# mt10_redraw.net
KiCad netlist of a schematic drawn in EAGLE
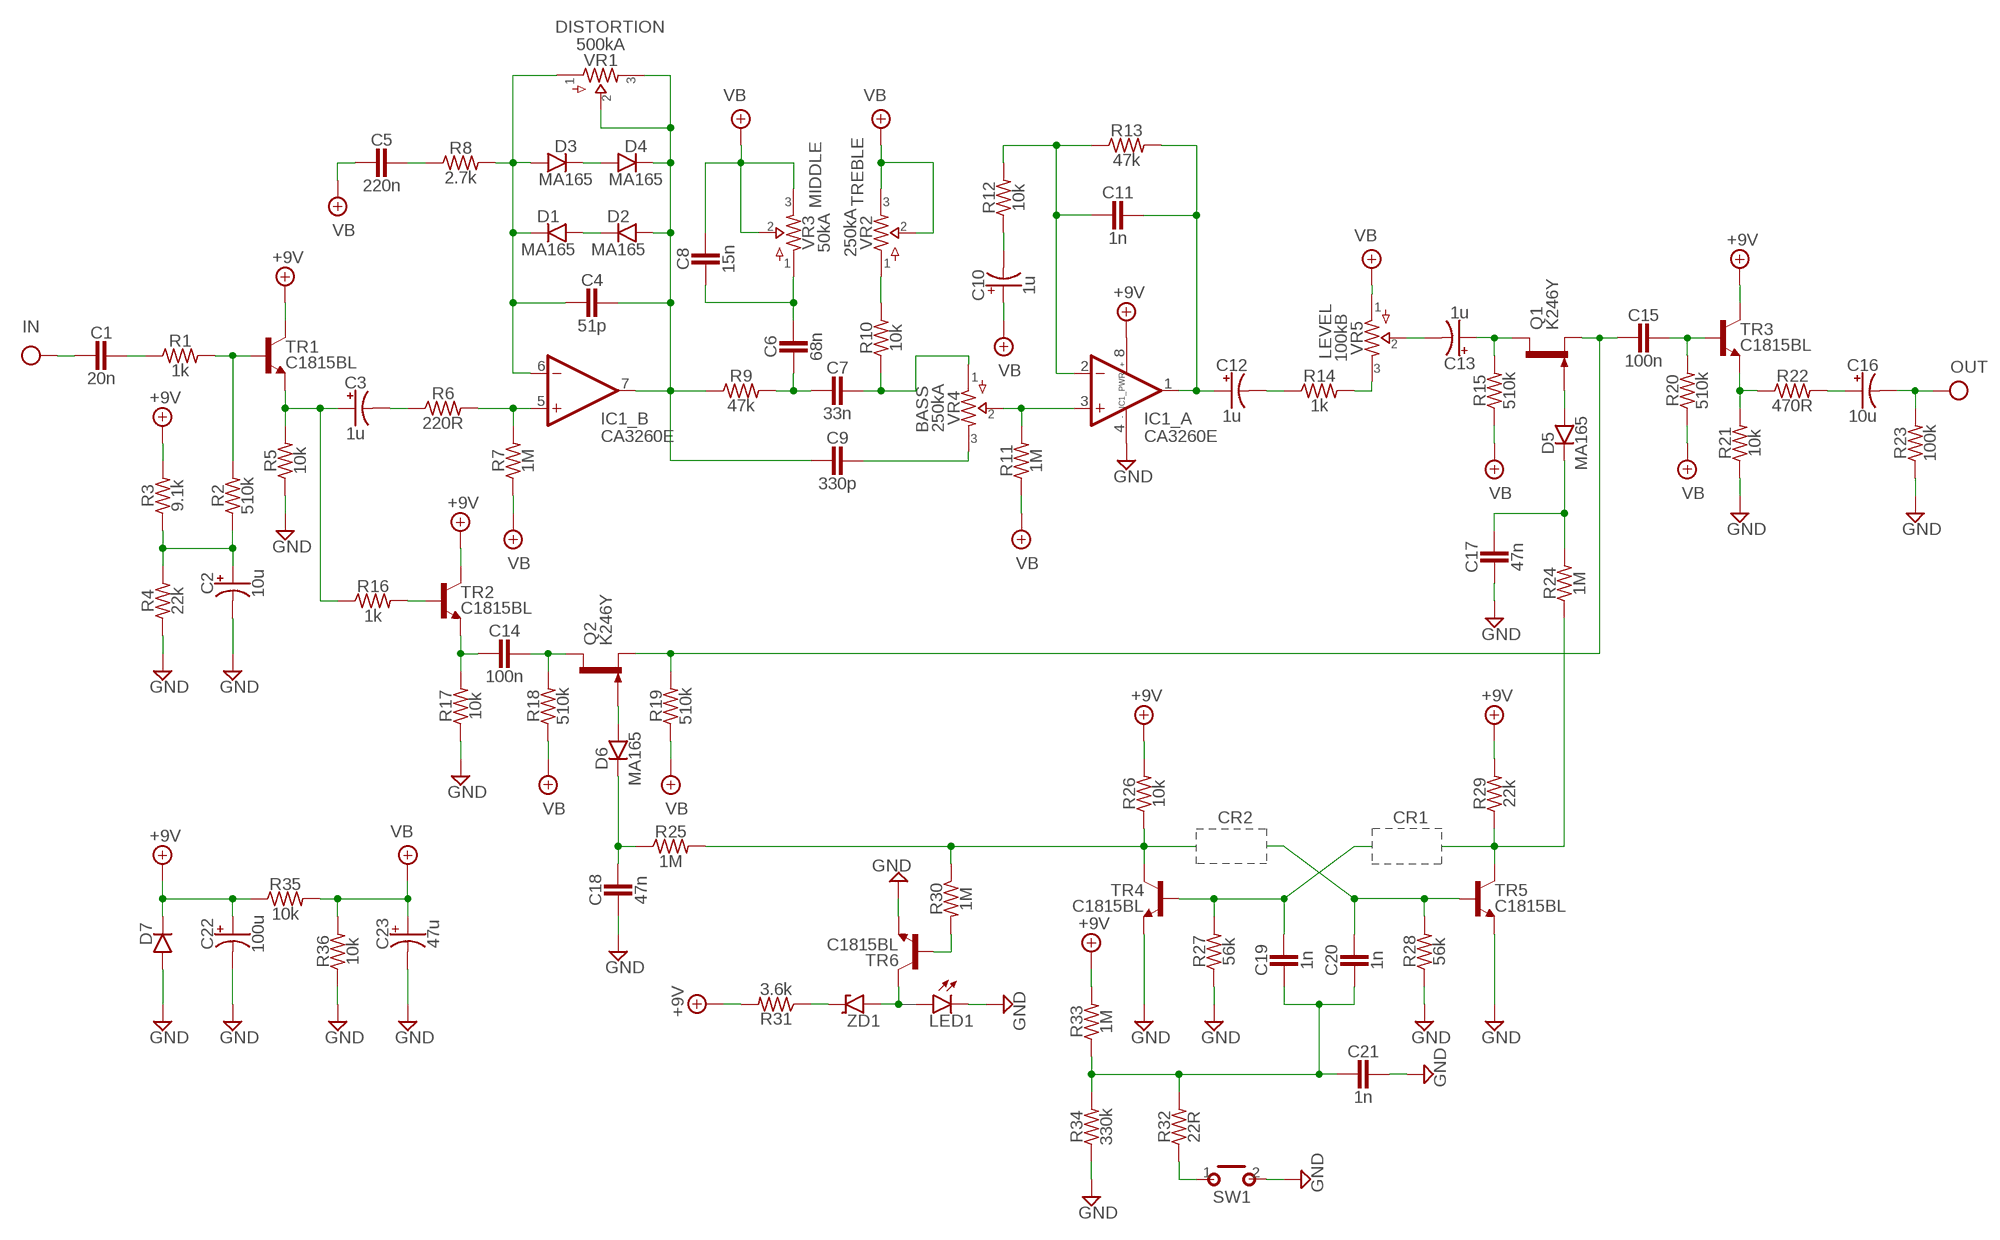
[diagram p0: schematic, sheet 1]

(export (version "E")
  (design (tool "Eeschema 10.0.6"))
  (components
    (comp (ref "C1")
      (value "20n")
      (footprint "eagle-import:BOX_SMALL")
      (libsource (lib "eagle-import") (part "CER/FILMBOX.1"))
    )
    (comp (ref "C2")
      (value "10u")
      (footprint "eagle-import:050_020")
      (libsource (lib "eagle-import") (part "0500"))
    )
    (comp (ref "C3")
      (value "1u")
      (footprint "eagle-import:050_020")
      (libsource (lib "eagle-import") (part "0500"))
    )
    (comp (ref "C4")
      (value "51p")
      (footprint "eagle-import:BOX_SMALL")
      (libsource (lib "eagle-import") (part "CER/FILMBOX.1"))
    )
    (comp (ref "C5")
      (value "220n")
      (footprint "eagle-import:BOX_SMALL")
      (libsource (lib "eagle-import") (part "CER/FILMBOX.1"))
    )
    (comp (ref "C6")
      (value "68n")
      (footprint "eagle-import:BOX_SMALL")
      (libsource (lib "eagle-import") (part "CER/FILMBOX.1"))
    )
    (comp (ref "C7")
      (value "33n")
      (footprint "eagle-import:BOX_SMALL")
      (libsource (lib "eagle-import") (part "CER/FILMBOX.1"))
    )
    (comp (ref "C8")
      (value "15n")
      (footprint "eagle-import:BOX_SMALL")
      (libsource (lib "eagle-import") (part "CER/FILMBOX.1"))
    )
    (comp (ref "C9")
      (value "330p")
      (footprint "eagle-import:BOX_SMALL")
      (libsource (lib "eagle-import") (part "CER/FILMBOX.1"))
    )
    (comp (ref "C10")
      (value "1u")
      (footprint "eagle-import:050_020")
      (libsource (lib "eagle-import") (part "0500"))
    )
    (comp (ref "C11")
      (value "1n")
      (footprint "eagle-import:BOX_SMALL")
      (libsource (lib "eagle-import") (part "CER/FILMBOX.1"))
    )
    (comp (ref "C12")
      (value "1u")
      (footprint "eagle-import:050_020")
      (libsource (lib "eagle-import") (part "0500"))
    )
    (comp (ref "C13")
      (value "1u")
      (footprint "eagle-import:050_020")
      (libsource (lib "eagle-import") (part "0500"))
    )
    (comp (ref "C14")
      (value "100n")
      (footprint "eagle-import:BOX_SMALL")
      (libsource (lib "eagle-import") (part "CER/FILMBOX.1"))
    )
    (comp (ref "C15")
      (value "100n")
      (footprint "eagle-import:BOX_SMALL")
      (libsource (lib "eagle-import") (part "CER/FILMBOX.1"))
    )
    (comp (ref "C16")
      (value "10u")
      (footprint "eagle-import:050_020")
      (libsource (lib "eagle-import") (part "0500"))
    )
    (comp (ref "C17")
      (value "47n")
      (footprint "eagle-import:BOX_SMALL")
      (libsource (lib "eagle-import") (part "CER/FILMBOX.1"))
    )
    (comp (ref "C18")
      (value "47n")
      (footprint "eagle-import:BOX_SMALL")
      (libsource (lib "eagle-import") (part "CER/FILMBOX.1"))
    )
    (comp (ref "C19")
      (value "1n")
      (footprint "eagle-import:BOX_SMALL")
      (libsource (lib "eagle-import") (part "CER/FILMBOX.1"))
    )
    (comp (ref "C20")
      (value "1n")
      (footprint "eagle-import:BOX_SMALL")
      (libsource (lib "eagle-import") (part "CER/FILMBOX.1"))
    )
    (comp (ref "C21")
      (value "1n")
      (footprint "eagle-import:BOX_SMALL")
      (libsource (lib "eagle-import") (part "CER/FILMBOX.1"))
    )
    (comp (ref "C22")
      (value "100u")
      (footprint "eagle-import:050_020")
      (libsource (lib "eagle-import") (part "0500"))
    )
    (comp (ref "C23")
      (value "47u")
      (footprint "eagle-import:050_020")
      (libsource (lib "eagle-import") (part "0500"))
    )
    (comp (ref "D1")
      (value "MA165")
      (footprint "eagle-import:DO35-2")
      (libsource (lib "eagle-import") (part "DO35.2"))
    )
    (comp (ref "D2")
      (value "MA165")
      (footprint "eagle-import:DO35-2")
      (libsource (lib "eagle-import") (part "DO35.2"))
    )
    (comp (ref "D3")
      (value "MA165")
      (footprint "eagle-import:DO35-2")
      (libsource (lib "eagle-import") (part "DO35.2"))
    )
    (comp (ref "D4")
      (value "MA165")
      (footprint "eagle-import:DO35-2")
      (libsource (lib "eagle-import") (part "DO35.2"))
    )
    (comp (ref "D5")
      (value "MA165")
      (footprint "eagle-import:DO35-2")
      (libsource (lib "eagle-import") (part "DO35.2"))
    )
    (comp (ref "D6")
      (value "MA165")
      (footprint "eagle-import:DO35-2")
      (libsource (lib "eagle-import") (part "DO35.2"))
    )
    (comp (ref "D7")
      (value "DO35.2")
      (footprint "eagle-import:DO35-2")
      (libsource (lib "eagle-import") (part "DO35.2"))
    )
    (comp (ref "IC1")
      (value "CA3260E")
      (footprint "eagle-import:DIL0")
      (libsource (lib "eagle-import") (part "DUALTH"))
    )
    (comp (ref "LED1")
      (value "LED")
      (footprint "eagle-import:3MM_D")
      (libsource (lib "eagle-import") (part "LED"))
    )
    (comp (ref "Q1")
      (value "K246Y")
      (footprint "eagle-import:TO92-")
      (libsource (lib "eagle-import") (part "2N5457"))
    )
    (comp (ref "Q2")
      (value "K246Y")
      (footprint "eagle-import:TO92-")
      (libsource (lib "eagle-import") (part "2N5457"))
    )
    (comp (ref "R1")
      (value "1k")
      (footprint "eagle-import:R0207_3")
      (libsource (lib "eagle-import") (part "R_.3B"))
    )
    (comp (ref "R2")
      (value "510k")
      (footprint "eagle-import:R0207_3")
      (libsource (lib "eagle-import") (part "R_.3B"))
    )
    (comp (ref "R3")
      (value "9.1k")
      (footprint "eagle-import:R0207_3")
      (libsource (lib "eagle-import") (part "R_.3B"))
    )
    (comp (ref "R4")
      (value "22k")
      (footprint "eagle-import:R0207_3")
      (libsource (lib "eagle-import") (part "R_.3B"))
    )
    (comp (ref "R5")
      (value "10k")
      (footprint "eagle-import:R0207_3")
      (libsource (lib "eagle-import") (part "R_.3B"))
    )
    (comp (ref "R6")
      (value "220R")
      (footprint "eagle-import:R0207_3")
      (libsource (lib "eagle-import") (part "R_.3B"))
    )
    (comp (ref "R7")
      (value "1M")
      (footprint "eagle-import:R0207_3")
      (libsource (lib "eagle-import") (part "R_.3B"))
    )
    (comp (ref "R8")
      (value "2.7k")
      (footprint "eagle-import:R0207_3")
      (libsource (lib "eagle-import") (part "R_.3B"))
    )
    (comp (ref "R9")
      (value "47k")
      (footprint "eagle-import:R0207_3")
      (libsource (lib "eagle-import") (part "R_.3B"))
    )
    (comp (ref "R10")
      (value "10k")
      (footprint "eagle-import:R0207_3")
      (libsource (lib "eagle-import") (part "R_.3B"))
    )
    (comp (ref "R11")
      (value "1M")
      (footprint "eagle-import:R0207_3")
      (libsource (lib "eagle-import") (part "R_.3B"))
    )
    (comp (ref "R12")
      (value "10k")
      (footprint "eagle-import:R0207_3")
      (libsource (lib "eagle-import") (part "R_.3B"))
    )
    (comp (ref "R13")
      (value "47k")
      (footprint "eagle-import:R0207_3")
      (libsource (lib "eagle-import") (part "R_.3B"))
    )
    (comp (ref "R14")
      (value "1k")
      (footprint "eagle-import:R0207_3")
      (libsource (lib "eagle-import") (part "R_.3B"))
    )
    (comp (ref "R15")
      (value "510k")
      (footprint "eagle-import:R0207_3")
      (libsource (lib "eagle-import") (part "R_.3B"))
    )
    (comp (ref "R16")
      (value "1k")
      (footprint "eagle-import:R0207_3")
      (libsource (lib "eagle-import") (part "R_.3B"))
    )
    (comp (ref "R17")
      (value "10k")
      (footprint "eagle-import:R0207_3")
      (libsource (lib "eagle-import") (part "R_.3B"))
    )
    (comp (ref "R18")
      (value "510k")
      (footprint "eagle-import:R0207_3")
      (libsource (lib "eagle-import") (part "R_.3B"))
    )
    (comp (ref "R19")
      (value "510k")
      (footprint "eagle-import:R0207_3")
      (libsource (lib "eagle-import") (part "R_.3B"))
    )
    (comp (ref "R20")
      (value "510k")
      (footprint "eagle-import:R0207_3")
      (libsource (lib "eagle-import") (part "R_.3B"))
    )
    (comp (ref "R21")
      (value "10k")
      (footprint "eagle-import:R0207_3")
      (libsource (lib "eagle-import") (part "R_.3B"))
    )
    (comp (ref "R22")
      (value "470R")
      (footprint "eagle-import:R0207_3")
      (libsource (lib "eagle-import") (part "R_.3B"))
    )
    (comp (ref "R23")
      (value "100k")
      (footprint "eagle-import:R0207_3")
      (libsource (lib "eagle-import") (part "R_.3B"))
    )
    (comp (ref "R24")
      (value "1M")
      (footprint "eagle-import:R0207_3")
      (libsource (lib "eagle-import") (part "R_.3B"))
    )
    (comp (ref "R25")
      (value "1M")
      (footprint "eagle-import:R0207_3")
      (libsource (lib "eagle-import") (part "R_.3B"))
    )
    (comp (ref "R26")
      (value "10k")
      (footprint "eagle-import:R0207_3")
      (libsource (lib "eagle-import") (part "R_.3B"))
    )
    (comp (ref "R27")
      (value "56k")
      (footprint "eagle-import:R0207_3")
      (libsource (lib "eagle-import") (part "R_.3B"))
    )
    (comp (ref "R28")
      (value "56k")
      (footprint "eagle-import:R0207_3")
      (libsource (lib "eagle-import") (part "R_.3B"))
    )
    (comp (ref "R29")
      (value "22k")
      (footprint "eagle-import:R0207_3")
      (libsource (lib "eagle-import") (part "R_.3B"))
    )
    (comp (ref "R30")
      (value "1M")
      (footprint "eagle-import:R0207_3")
      (libsource (lib "eagle-import") (part "R_.3B"))
    )
    (comp (ref "R31")
      (value "3.6k")
      (footprint "eagle-import:R0207_3")
      (libsource (lib "eagle-import") (part "R_.3B"))
    )
    (comp (ref "R32")
      (value "22R")
      (footprint "eagle-import:R0207_3")
      (libsource (lib "eagle-import") (part "R_.3B"))
    )
    (comp (ref "R33")
      (value "1M")
      (footprint "eagle-import:R0207_3")
      (libsource (lib "eagle-import") (part "R_.3B"))
    )
    (comp (ref "R34")
      (value "330k")
      (footprint "eagle-import:R0207_3")
      (libsource (lib "eagle-import") (part "R_.3B"))
    )
    (comp (ref "R35")
      (value "10k")
      (footprint "eagle-import:R0207_3")
      (libsource (lib "eagle-import") (part "R_.3B"))
    )
    (comp (ref "R36")
      (value "10k")
      (footprint "eagle-import:R0207_3")
      (libsource (lib "eagle-import") (part "R_.3B"))
    )
    (comp (ref "SW1")
      (value "MOMENTARY")
      (footprint "eagle-import:SPST")
      (libsource (lib "eagle-import") (part "MOMENTARY"))
    )
    (comp (ref "TR1")
      (value "C1815BL")
      (footprint "eagle-import:TO92-")
      (libsource (lib "eagle-import") (part "2SC828A"))
    )
    (comp (ref "TR2")
      (value "C1815BL")
      (footprint "eagle-import:TO92-")
      (libsource (lib "eagle-import") (part "2SC828A"))
    )
    (comp (ref "TR3")
      (value "C1815BL")
      (footprint "eagle-import:TO92-")
      (libsource (lib "eagle-import") (part "2SC828A"))
    )
    (comp (ref "TR4")
      (value "C1815BL")
      (footprint "eagle-import:TO92-")
      (libsource (lib "eagle-import") (part "2SC828A"))
    )
    (comp (ref "TR5")
      (value "C1815BL")
      (footprint "eagle-import:TO92-")
      (libsource (lib "eagle-import") (part "2SC828A"))
    )
    (comp (ref "TR6")
      (value "C1815BL")
      (footprint "eagle-import:TO92-")
      (libsource (lib "eagle-import") (part "2SC828A"))
    )
    (comp (ref "VR1")
      (value "500kA")
      (footprint "eagle-import:16MM")
      (libsource (lib "eagle-import") (part "POTS16MM"))
    )
    (comp (ref "VR2")
      (value "250kA")
      (footprint "eagle-import:16MM")
      (libsource (lib "eagle-import") (part "POTS16MM"))
    )
    (comp (ref "VR3")
      (value "50kA")
      (footprint "eagle-import:16MM")
      (libsource (lib "eagle-import") (part "POTS16MM"))
    )
    (comp (ref "VR4")
      (value "250kA")
      (footprint "eagle-import:16MM")
      (libsource (lib "eagle-import") (part "POTS16MM"))
    )
    (comp (ref "VR5")
      (value "100kB")
      (footprint "eagle-import:16MM")
      (libsource (lib "eagle-import") (part "POTS16MM"))
    )
    (comp (ref "ZD1")
      (value "ZENER.1")
      (footprint "eagle-import:DO41-1")
      (libsource (lib "eagle-import") (part "ZENER.1"))
    )
  )
  (nets
    (net (code "1") (name "+9V") (class "Default")
      (node (ref "C22") (pin "+") (pinfunction "+_+") (pintype "passive"))
      (node (ref "D7") (pin "C") (pinfunction "C_C") (pintype "passive"))
      (node (ref "IC1") (pin "8") (pinfunction "V+_8") (pintype "power_in"))
      (node (ref "R26") (pin "2") (pinfunction "2_2") (pintype "passive"))
      (node (ref "R29") (pin "2") (pinfunction "2_2") (pintype "passive"))
      (node (ref "R3") (pin "2") (pinfunction "2_2") (pintype "passive"))
      (node (ref "R31") (pin "2") (pinfunction "2_2") (pintype "passive"))
      (node (ref "R33") (pin "2") (pinfunction "2_2") (pintype "passive"))
      (node (ref "R35") (pin "1") (pinfunction "1_1") (pintype "passive"))
      (node (ref "TR1") (pin "2") (pinfunction "C_2") (pintype "passive"))
      (node (ref "TR2") (pin "2") (pinfunction "C_2") (pintype "passive"))
      (node (ref "TR3") (pin "2") (pinfunction "C_2") (pintype "passive"))
    )
    (net (code "2") (name "GND") (class "Default")
      (node (ref "C17") (pin "2") (pinfunction "2_2") (pintype "passive"))
      (node (ref "C18") (pin "2") (pinfunction "2_2") (pintype "passive"))
      (node (ref "C2") (pin "-") (pinfunction "-_-") (pintype "passive"))
      (node (ref "C21") (pin "2") (pinfunction "2_2") (pintype "passive"))
      (node (ref "C22") (pin "-") (pinfunction "-_-") (pintype "passive"))
      (node (ref "C23") (pin "-") (pinfunction "-_-") (pintype "passive"))
      (node (ref "D7") (pin "A") (pinfunction "A_A") (pintype "passive"))
      (node (ref "IC1") (pin "4") (pinfunction "V-_4") (pintype "power_in"))
      (node (ref "LED1") (pin "P$1") (pinfunction "C_P$1") (pintype "passive"))
      (node (ref "R17") (pin "1") (pinfunction "1_1") (pintype "passive"))
      (node (ref "R21") (pin "1") (pinfunction "1_1") (pintype "passive"))
      (node (ref "R23") (pin "1") (pinfunction "1_1") (pintype "passive"))
      (node (ref "R27") (pin "1") (pinfunction "1_1") (pintype "passive"))
      (node (ref "R28") (pin "1") (pinfunction "1_1") (pintype "passive"))
      (node (ref "R34") (pin "1") (pinfunction "1_1") (pintype "passive"))
      (node (ref "R36") (pin "1") (pinfunction "1_1") (pintype "passive"))
      (node (ref "R4") (pin "1") (pinfunction "1_1") (pintype "passive"))
      (node (ref "R5") (pin "1") (pinfunction "1_1") (pintype "passive"))
      (node (ref "SW1") (pin "2") (pinfunction "S_2") (pintype "passive"))
      (node (ref "TR4") (pin "3") (pinfunction "E_3") (pintype "passive"))
      (node (ref "TR5") (pin "3") (pinfunction "E_3") (pintype "passive"))
      (node (ref "TR6") (pin "3") (pinfunction "E_3") (pintype "passive"))
    )
    (net (code "3") (name "IN") (class "Default")
      (node (ref "C1") (pin "2") (pinfunction "2_2") (pintype "passive"))
    )
    (net (code "4") (name "Net-(C1-Pad1)") (class "Default")
      (node (ref "C1") (pin "1") (pinfunction "1_1") (pintype "passive"))
      (node (ref "R1") (pin "1") (pinfunction "1_1") (pintype "passive"))
    )
    (net (code "5") (name "Net-(C2-Pad+)") (class "Default")
      (node (ref "C2") (pin "+") (pinfunction "+_+") (pintype "passive"))
      (node (ref "R2") (pin "1") (pinfunction "1_1") (pintype "passive"))
      (node (ref "R3") (pin "1") (pinfunction "1_1") (pintype "passive"))
      (node (ref "R4") (pin "2") (pinfunction "2_2") (pintype "passive"))
    )
    (net (code "6") (name "Net-(C3-Pad-)") (class "Default")
      (node (ref "C3") (pin "-") (pinfunction "-_-") (pintype "passive"))
      (node (ref "R6") (pin "1") (pinfunction "1_1") (pintype "passive"))
    )
    (net (code "7") (name "Net-(C5-Pad1)") (class "Default")
      (node (ref "C5") (pin "1") (pinfunction "1_1") (pintype "passive"))
      (node (ref "R8") (pin "1") (pinfunction "1_1") (pintype "passive"))
    )
    (net (code "8") (name "Net-(C6-Pad1)") (class "Default")
      (node (ref "C6") (pin "1") (pinfunction "1_1") (pintype "passive"))
      (node (ref "C8") (pin "2") (pinfunction "2_2") (pintype "passive"))
      (node (ref "VR3") (pin "1") (pinfunction "1_1") (pintype "passive"))
    )
    (net (code "9") (name "Net-(C6-Pad2)") (class "Default")
      (node (ref "C6") (pin "2") (pinfunction "2_2") (pintype "passive"))
      (node (ref "C7") (pin "2") (pinfunction "2_2") (pintype "passive"))
      (node (ref "R9") (pin "2") (pinfunction "2_2") (pintype "passive"))
    )
    (net (code "10") (name "Net-(C7-Pad1)") (class "Default")
      (node (ref "C7") (pin "1") (pinfunction "1_1") (pintype "passive"))
      (node (ref "R10") (pin "1") (pinfunction "1_1") (pintype "passive"))
      (node (ref "VR4") (pin "1") (pinfunction "1_1") (pintype "passive"))
    )
    (net (code "11") (name "Net-(C9-Pad1)") (class "Default")
      (node (ref "C9") (pin "1") (pinfunction "1_1") (pintype "passive"))
      (node (ref "VR4") (pin "3") (pinfunction "3_3") (pintype "passive"))
    )
    (net (code "12") (name "Net-(C10-Pad-)") (class "Default")
      (node (ref "C10") (pin "-") (pinfunction "-_-") (pintype "passive"))
      (node (ref "R12") (pin "1") (pinfunction "1_1") (pintype "passive"))
    )
    (net (code "13") (name "Net-(C12-Pad-)") (class "Default")
      (node (ref "C12") (pin "-") (pinfunction "-_-") (pintype "passive"))
      (node (ref "R14") (pin "1") (pinfunction "1_1") (pintype "passive"))
    )
    (net (code "14") (name "Net-(C13-Pad-)") (class "Default")
      (node (ref "C13") (pin "-") (pinfunction "-_-") (pintype "passive"))
      (node (ref "VR5") (pin "2") (pinfunction "2_2") (pintype "passive"))
    )
    (net (code "15") (name "Net-(C16-Pad+)") (class "Default")
      (node (ref "C16") (pin "+") (pinfunction "+_+") (pintype "passive"))
      (node (ref "R22") (pin "2") (pinfunction "2_2") (pintype "passive"))
    )
    (net (code "16") (name "Net-(C17-Pad1)") (class "Default")
      (node (ref "C17") (pin "1") (pinfunction "1_1") (pintype "passive"))
      (node (ref "D5") (pin "C") (pinfunction "C_C") (pintype "passive"))
      (node (ref "R24") (pin "2") (pinfunction "2_2") (pintype "passive"))
    )
    (net (code "17") (name "Net-(C18-Pad1)") (class "Default")
      (node (ref "C18") (pin "1") (pinfunction "1_1") (pintype "passive"))
      (node (ref "D6") (pin "C") (pinfunction "C_C") (pintype "passive"))
      (node (ref "R25") (pin "1") (pinfunction "1_1") (pintype "passive"))
    )
    (net (code "18") (name "Net-(C19-Pad2)") (class "Default")
      (node (ref "C19") (pin "2") (pinfunction "2_2") (pintype "passive"))
      (node (ref "C20") (pin "2") (pinfunction "2_2") (pintype "passive"))
      (node (ref "C21") (pin "1") (pinfunction "1_1") (pintype "passive"))
      (node (ref "R32") (pin "2") (pinfunction "2_2") (pintype "passive"))
      (node (ref "R33") (pin "1") (pinfunction "1_1") (pintype "passive"))
      (node (ref "R34") (pin "2") (pinfunction "2_2") (pintype "passive"))
    )
    (net (code "19") (name "Net-(D1-PadA)") (class "Default")
      (node (ref "D1") (pin "A") (pinfunction "A_A") (pintype "passive"))
      (node (ref "D2") (pin "C") (pinfunction "C_C") (pintype "passive"))
    )
    (net (code "20") (name "Net-(D3-PadC)") (class "Default")
      (node (ref "D3") (pin "C") (pinfunction "C_C") (pintype "passive"))
      (node (ref "D4") (pin "A") (pinfunction "A_A") (pintype "passive"))
    )
    (net (code "21") (name "Net-(IC1A-+IN)") (class "Default")
      (node (ref "IC1") (pin "3") (pinfunction "+IN_3") (pintype "input"))
      (node (ref "R11") (pin "2") (pinfunction "2_2") (pintype "passive"))
      (node (ref "VR4") (pin "2") (pinfunction "2_2") (pintype "passive"))
    )
    (net (code "22") (name "Net-(IC1A--IN)") (class "Default")
      (node (ref "C11") (pin "2") (pinfunction "2_2") (pintype "passive"))
      (node (ref "IC1") (pin "2") (pinfunction "-IN_2") (pintype "input"))
      (node (ref "R12") (pin "2") (pinfunction "2_2") (pintype "passive"))
      (node (ref "R13") (pin "1") (pinfunction "1_1") (pintype "passive"))
    )
    (net (code "23") (name "Net-(IC1A-OUT)") (class "Default")
      (node (ref "C11") (pin "1") (pinfunction "1_1") (pintype "passive"))
      (node (ref "C12") (pin "+") (pinfunction "+_+") (pintype "passive"))
      (node (ref "IC1") (pin "1") (pinfunction "OUT_1") (pintype "output"))
      (node (ref "R13") (pin "2") (pinfunction "2_2") (pintype "passive"))
    )
    (net (code "24") (name "Net-(IC1B-+IN)") (class "Default")
      (node (ref "IC1") (pin "5") (pinfunction "+IN_5") (pintype "input"))
      (node (ref "R6") (pin "2") (pinfunction "2_2") (pintype "passive"))
      (node (ref "R7") (pin "2") (pinfunction "2_2") (pintype "passive"))
    )
    (net (code "25") (name "Net-(IC1B--IN)") (class "Default")
      (node (ref "C4") (pin "2") (pinfunction "2_2") (pintype "passive"))
      (node (ref "D1") (pin "C") (pinfunction "C_C") (pintype "passive"))
      (node (ref "D3") (pin "A") (pinfunction "A_A") (pintype "passive"))
      (node (ref "IC1") (pin "6") (pinfunction "-IN_6") (pintype "input"))
      (node (ref "R8") (pin "2") (pinfunction "2_2") (pintype "passive"))
      (node (ref "VR1") (pin "1") (pinfunction "1_1") (pintype "passive"))
    )
    (net (code "26") (name "Net-(IC1B-OUT)") (class "Default")
      (node (ref "C4") (pin "1") (pinfunction "1_1") (pintype "passive"))
      (node (ref "C9") (pin "2") (pinfunction "2_2") (pintype "passive"))
      (node (ref "D2") (pin "A") (pinfunction "A_A") (pintype "passive"))
      (node (ref "D4") (pin "C") (pinfunction "C_C") (pintype "passive"))
      (node (ref "IC1") (pin "7") (pinfunction "OUT_7") (pintype "output"))
      (node (ref "R9") (pin "1") (pinfunction "1_1") (pintype "passive"))
      (node (ref "VR1") (pin "2") (pinfunction "2_2") (pintype "passive"))
      (node (ref "VR1") (pin "3") (pinfunction "3_3") (pintype "passive"))
    )
    (net (code "27") (name "Net-(Q1-D)") (class "Default")
      (node (ref "C13") (pin "+") (pinfunction "+_+") (pintype "passive"))
      (node (ref "Q1") (pin "3") (pinfunction "D_3") (pintype "passive"))
      (node (ref "R15") (pin "2") (pinfunction "2_2") (pintype "passive"))
    )
    (net (code "28") (name "Net-(Q1-G)") (class "Default")
      (node (ref "D5") (pin "A") (pinfunction "A_A") (pintype "passive"))
      (node (ref "Q1") (pin "1") (pinfunction "G_1") (pintype "passive"))
    )
    (net (code "29") (name "Net-(Q1-S)") (class "Default")
      (node (ref "C15") (pin "2") (pinfunction "2_2") (pintype "passive"))
      (node (ref "Q1") (pin "2") (pinfunction "S_2") (pintype "passive"))
      (node (ref "Q2") (pin "2") (pinfunction "S_2") (pintype "passive"))
      (node (ref "R19") (pin "2") (pinfunction "2_2") (pintype "passive"))
    )
    (net (code "30") (name "Net-(Q2-D)") (class "Default")
      (node (ref "C14") (pin "1") (pinfunction "1_1") (pintype "passive"))
      (node (ref "Q2") (pin "3") (pinfunction "D_3") (pintype "passive"))
      (node (ref "R18") (pin "2") (pinfunction "2_2") (pintype "passive"))
    )
    (net (code "31") (name "Net-(Q2-G)") (class "Default")
      (node (ref "D6") (pin "A") (pinfunction "A_A") (pintype "passive"))
      (node (ref "Q2") (pin "1") (pinfunction "G_1") (pintype "passive"))
    )
    (net (code "32") (name "Net-(R10-Pad2)") (class "Default")
      (node (ref "R10") (pin "2") (pinfunction "2_2") (pintype "passive"))
      (node (ref "VR2") (pin "1") (pinfunction "1_1") (pintype "passive"))
    )
    (net (code "33") (name "Net-(R14-Pad2)") (class "Default")
      (node (ref "R14") (pin "2") (pinfunction "2_2") (pintype "passive"))
      (node (ref "VR5") (pin "3") (pinfunction "3_3") (pintype "passive"))
    )
    (net (code "34") (name "Net-(R31-Pad1)") (class "Default")
      (node (ref "R31") (pin "1") (pinfunction "1_1") (pintype "passive"))
      (node (ref "ZD1") (pin "C") (pinfunction "C_C") (pintype "passive"))
    )
    (net (code "35") (name "Net-(SW1-P)") (class "Default")
      (node (ref "R32") (pin "1") (pinfunction "1_1") (pintype "passive"))
      (node (ref "SW1") (pin "1") (pinfunction "P_1") (pintype "passive"))
    )
    (net (code "36") (name "Net-(TR1-B)") (class "Default")
      (node (ref "R1") (pin "2") (pinfunction "2_2") (pintype "passive"))
      (node (ref "R2") (pin "2") (pinfunction "2_2") (pintype "passive"))
      (node (ref "TR1") (pin "1") (pinfunction "B_1") (pintype "passive"))
    )
    (net (code "37") (name "Net-(TR1-E)") (class "Default")
      (node (ref "C3") (pin "+") (pinfunction "+_+") (pintype "passive"))
      (node (ref "R16") (pin "1") (pinfunction "1_1") (pintype "passive"))
      (node (ref "R5") (pin "2") (pinfunction "2_2") (pintype "passive"))
      (node (ref "TR1") (pin "3") (pinfunction "E_3") (pintype "passive"))
    )
    (net (code "38") (name "Net-(TR2-B)") (class "Default")
      (node (ref "R16") (pin "2") (pinfunction "2_2") (pintype "passive"))
      (node (ref "TR2") (pin "1") (pinfunction "B_1") (pintype "passive"))
    )
    (net (code "39") (name "Net-(TR2-E)") (class "Default")
      (node (ref "C14") (pin "2") (pinfunction "2_2") (pintype "passive"))
      (node (ref "R17") (pin "2") (pinfunction "2_2") (pintype "passive"))
      (node (ref "TR2") (pin "3") (pinfunction "E_3") (pintype "passive"))
    )
    (net (code "40") (name "Net-(TR3-B)") (class "Default")
      (node (ref "C15") (pin "1") (pinfunction "1_1") (pintype "passive"))
      (node (ref "R20") (pin "2") (pinfunction "2_2") (pintype "passive"))
      (node (ref "TR3") (pin "1") (pinfunction "B_1") (pintype "passive"))
    )
    (net (code "41") (name "Net-(TR3-E)") (class "Default")
      (node (ref "R21") (pin "2") (pinfunction "2_2") (pintype "passive"))
      (node (ref "R22") (pin "1") (pinfunction "1_1") (pintype "passive"))
      (node (ref "TR3") (pin "3") (pinfunction "E_3") (pintype "passive"))
    )
    (net (code "42") (name "Net-(TR4-B)") (class "Default")
      (node (ref "C19") (pin "1") (pinfunction "1_1") (pintype "passive"))
      (node (ref "R27") (pin "2") (pinfunction "2_2") (pintype "passive"))
      (node (ref "TR4") (pin "1") (pinfunction "B_1") (pintype "passive"))
    )
    (net (code "43") (name "Net-(TR4-C)") (class "Default")
      (node (ref "R25") (pin "2") (pinfunction "2_2") (pintype "passive"))
      (node (ref "R26") (pin "1") (pinfunction "1_1") (pintype "passive"))
      (node (ref "R30") (pin "1") (pinfunction "1_1") (pintype "passive"))
      (node (ref "TR4") (pin "2") (pinfunction "C_2") (pintype "passive"))
    )
    (net (code "44") (name "Net-(TR5-B)") (class "Default")
      (node (ref "C20") (pin "1") (pinfunction "1_1") (pintype "passive"))
      (node (ref "R28") (pin "2") (pinfunction "2_2") (pintype "passive"))
      (node (ref "TR5") (pin "1") (pinfunction "B_1") (pintype "passive"))
    )
    (net (code "45") (name "Net-(TR5-C)") (class "Default")
      (node (ref "R24") (pin "1") (pinfunction "1_1") (pintype "passive"))
      (node (ref "R29") (pin "1") (pinfunction "1_1") (pintype "passive"))
      (node (ref "TR5") (pin "2") (pinfunction "C_2") (pintype "passive"))
    )
    (net (code "46") (name "Net-(TR6-B)") (class "Default")
      (node (ref "R30") (pin "2") (pinfunction "2_2") (pintype "passive"))
      (node (ref "TR6") (pin "1") (pinfunction "B_1") (pintype "passive"))
    )
    (net (code "47") (name "Net-(TR6-C)") (class "Default")
      (node (ref "TR6") (pin "2") (pinfunction "C_2") (pintype "passive"))
      (node (ref "ZD1") (pin "A") (pinfunction "A_A") (pintype "passive"))
    )
    (net (code "48") (name "OUT") (class "Default")
      (node (ref "C16") (pin "-") (pinfunction "-_-") (pintype "passive"))
      (node (ref "R23") (pin "2") (pinfunction "2_2") (pintype "passive"))
    )
    (net (code "49") (name "VB") (class "Default")
      (node (ref "C10") (pin "+") (pinfunction "+_+") (pintype "passive"))
      (node (ref "C23") (pin "+") (pinfunction "+_+") (pintype "passive"))
      (node (ref "C5") (pin "2") (pinfunction "2_2") (pintype "passive"))
      (node (ref "C8") (pin "1") (pinfunction "1_1") (pintype "passive"))
      (node (ref "R11") (pin "1") (pinfunction "1_1") (pintype "passive"))
      (node (ref "R15") (pin "1") (pinfunction "1_1") (pintype "passive"))
      (node (ref "R18") (pin "1") (pinfunction "1_1") (pintype "passive"))
      (node (ref "R19") (pin "1") (pinfunction "1_1") (pintype "passive"))
      (node (ref "R20") (pin "1") (pinfunction "1_1") (pintype "passive"))
      (node (ref "R35") (pin "2") (pinfunction "2_2") (pintype "passive"))
      (node (ref "R36") (pin "2") (pinfunction "2_2") (pintype "passive"))
      (node (ref "R7") (pin "1") (pinfunction "1_1") (pintype "passive"))
      (node (ref "VR2") (pin "2") (pinfunction "2_2") (pintype "passive"))
      (node (ref "VR2") (pin "3") (pinfunction "3_3") (pintype "passive"))
      (node (ref "VR3") (pin "2") (pinfunction "2_2") (pintype "passive"))
      (node (ref "VR3") (pin "3") (pinfunction "3_3") (pintype "passive"))
      (node (ref "VR5") (pin "1") (pinfunction "1_1") (pintype "passive"))
    )
    (net (code "50") (name "unconnected-(LED1-A-PadANODE)") (class "Default")
      (node (ref "LED1") (pin "ANODE") (pinfunction "A_ANODE") (pintype "passive"))
    )
  )
)
